# ADSR_Waveform_v1_1.net
KiCad netlist of a schematic drawn in EAGLE
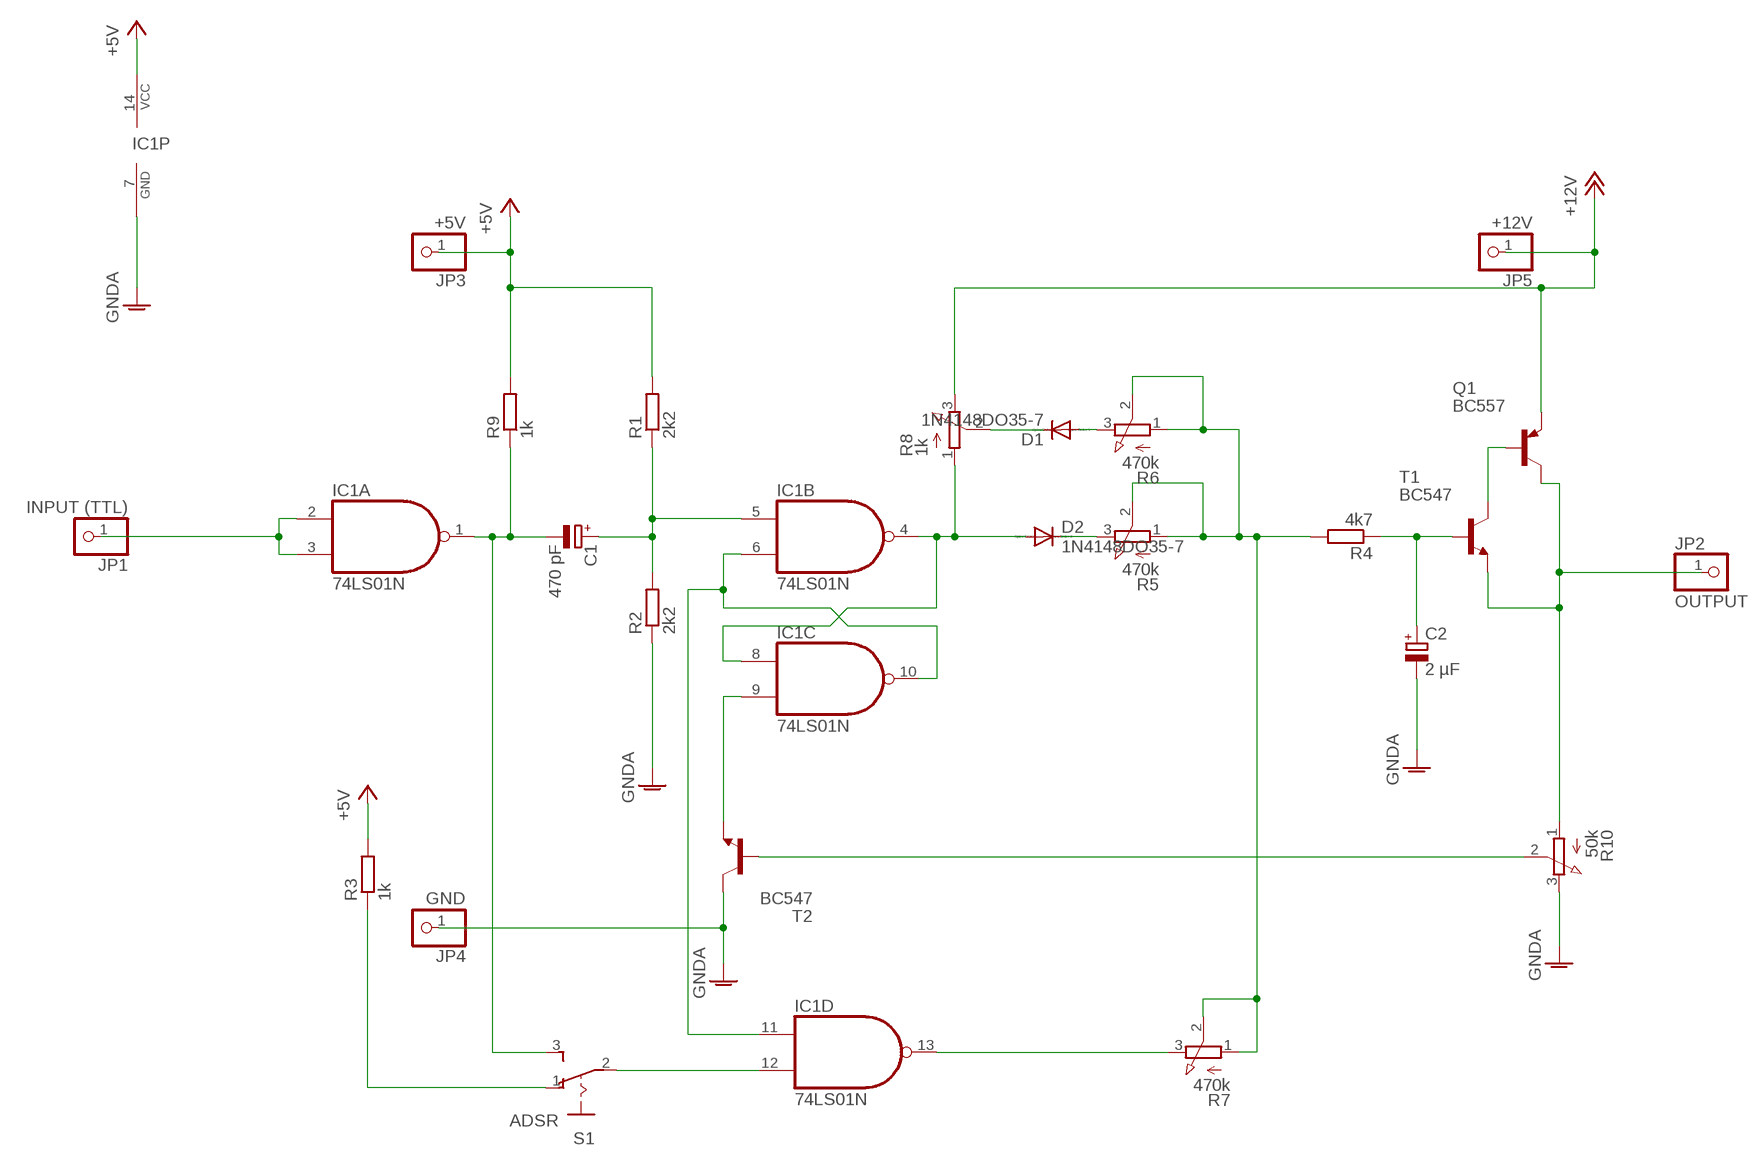
[diagram p0: schematic, sheet 1]

(export (version "E")
  (design (tool "Eeschema 10.0.6"))
  (components
    (comp (ref "C1")
      (value "470 pF")
      (footprint "eagle-import:E5-5")
      (libsource (lib "eagle-import") (part "CPOL-EUE5-5"))
    )
    (comp (ref "C2")
      (value "2 µF")
      (footprint "eagle-import:E5-5")
      (libsource (lib "eagle-import") (part "CPOL-EUE5-5"))
    )
    (comp (ref "D1")
      (value "1N4148DO35-7")
      (footprint "eagle-import:DO35-7")
      (libsource (lib "eagle-import") (part "1N4148DO35-7"))
    )
    (comp (ref "D2")
      (value "1N4148DO35-7")
      (footprint "eagle-import:DO35-7")
      (libsource (lib "eagle-import") (part "1N4148DO35-7"))
    )
    (comp (ref "IC1")
      (value "74LS01N")
      (footprint "eagle-import:DIL14")
      (libsource (lib "eagle-import") (part "7401NLS"))
    )
    (comp (ref "JP1")
      (value "INPUT (TTL)")
      (footprint "eagle-import:1X01")
      (libsource (lib "eagle-import") (part "PINHD-1X1"))
    )
    (comp (ref "JP2")
      (value "OUTPUT")
      (footprint "eagle-import:1X01")
      (libsource (lib "eagle-import") (part "PINHD-1X1"))
    )
    (comp (ref "JP3")
      (value "+5V")
      (footprint "eagle-import:1X01")
      (libsource (lib "eagle-import") (part "PINHD-1X1"))
    )
    (comp (ref "JP4")
      (value "GND")
      (footprint "eagle-import:1X01")
      (libsource (lib "eagle-import") (part "PINHD-1X1"))
    )
    (comp (ref "JP5")
      (value "+12V")
      (footprint "eagle-import:1X01")
      (libsource (lib "eagle-import") (part "PINHD-1X1"))
    )
    (comp (ref "Q1")
      (value "BC557")
      (footprint "eagle-import:TO92")
      (libsource (lib "eagle-import") (part "BC557"))
    )
    (comp (ref "R1")
      (value "2k2")
      (footprint "eagle-import:0204_5")
      (libsource (lib "eagle-import") (part "R-EU_0204/5"))
    )
    (comp (ref "R2")
      (value "2k2")
      (footprint "eagle-import:0204_5")
      (libsource (lib "eagle-import") (part "R-EU_0204/5"))
    )
    (comp (ref "R3")
      (value "1k")
      (footprint "eagle-import:0204_5")
      (libsource (lib "eagle-import") (part "R-EU_0204/5"))
    )
    (comp (ref "R4")
      (value "4k7")
      (footprint "eagle-import:0204_5")
      (libsource (lib "eagle-import") (part "R-EU_0204/5"))
    )
    (comp (ref "R5")
      (value "470k")
      (footprint "eagle-import:3RP_1610N")
      (libsource (lib "eagle-import") (part "3RP/1610N"))
    )
    (comp (ref "R6")
      (value "470k")
      (footprint "eagle-import:3RP_1610N")
      (libsource (lib "eagle-import") (part "3RP/1610N"))
    )
    (comp (ref "R7")
      (value "470k")
      (footprint "eagle-import:3RP_1610N")
      (libsource (lib "eagle-import") (part "3RP/1610N"))
    )
    (comp (ref "R8")
      (value "1k")
      (footprint "eagle-import:3RP_1610N")
      (libsource (lib "eagle-import") (part "3RP/1610N"))
    )
    (comp (ref "R9")
      (value "1k")
      (footprint "eagle-import:0204_5")
      (libsource (lib "eagle-import") (part "R-EU_0204/5"))
    )
    (comp (ref "R10")
      (value "50k")
      (footprint "eagle-import:3RP_1610N")
      (libsource (lib "eagle-import") (part "3RP/1610N"))
    )
    (comp (ref "S1")
      (value "ADSR")
      (footprint "eagle-import:255SB")
      (libsource (lib "eagle-import") (part "255SB"))
    )
    (comp (ref "T1")
      (value "BC547")
      (footprint "eagle-import:TO92")
      (libsource (lib "eagle-import") (part "BC547"))
    )
    (comp (ref "T2")
      (value "BC547")
      (footprint "eagle-import:TO92")
      (libsource (lib "eagle-import") (part "BC547"))
    )
  )
  (nets
    (net (code "1") (name "+5V") (class "Default")
      (node (ref "IC1") (pin "14") (pinfunction "VCC_14") (pintype "power_in"))
      (node (ref "JP3") (pin "1") (pinfunction "1_1") (pintype "passive"))
      (node (ref "R1") (pin "2") (pinfunction "2_2") (pintype "passive"))
      (node (ref "R3") (pin "2") (pinfunction "2_2") (pintype "passive"))
      (node (ref "R9") (pin "2") (pinfunction "2_2") (pintype "passive"))
    )
    (net (code "2") (name "+12V") (class "Default")
      (node (ref "JP5") (pin "1") (pinfunction "1_1") (pintype "passive"))
      (node (ref "Q1") (pin "1") (pinfunction "E_1") (pintype "passive"))
      (node (ref "R8") (pin "3") (pinfunction "E_3") (pintype "passive"))
    )
    (net (code "3") (name "GNDA") (class "Default")
      (node (ref "C2") (pin "-") (pinfunction "-_-") (pintype "passive"))
      (node (ref "IC1") (pin "7") (pinfunction "GND_7") (pintype "power_in"))
      (node (ref "JP4") (pin "1") (pinfunction "1_1") (pintype "passive"))
      (node (ref "R10") (pin "3") (pinfunction "E_3") (pintype "passive"))
      (node (ref "R2") (pin "1") (pinfunction "1_1") (pintype "passive"))
      (node (ref "T2") (pin "3") (pinfunction "C_3") (pintype "passive"))
    )
    (net (code "4") (name "Net-(IC1A-I0)") (class "Default")
      (node (ref "IC1") (pin "2") (pinfunction "I0_2") (pintype "input"))
      (node (ref "IC1") (pin "3") (pinfunction "I1_3") (pintype "input"))
      (node (ref "JP1") (pin "1") (pinfunction "1_1") (pintype "passive"))
    )
    (net (code "5") (name "Net-(IC1A-O)") (class "Default")
      (node (ref "C1") (pin "-") (pinfunction "-_-") (pintype "passive"))
      (node (ref "IC1") (pin "1") (pinfunction "O_1") (pintype "open_collector"))
      (node (ref "R9") (pin "1") (pinfunction "1_1") (pintype "passive"))
      (node (ref "S1") (pin "3") (pinfunction "S_3") (pintype "passive"))
    )
    (net (code "6") (name "Net-(IC1B-I0)") (class "Default")
      (node (ref "C1") (pin "+") (pinfunction "+_+") (pintype "passive"))
      (node (ref "IC1") (pin "5") (pinfunction "I0_5") (pintype "input"))
      (node (ref "R1") (pin "1") (pinfunction "1_1") (pintype "passive"))
      (node (ref "R2") (pin "2") (pinfunction "2_2") (pintype "passive"))
    )
    (net (code "7") (name "Net-(IC1B-I1)") (class "Default")
      (node (ref "IC1") (pin "10") (pinfunction "O_10") (pintype "open_collector"))
      (node (ref "IC1") (pin "11") (pinfunction "I0_11") (pintype "input"))
      (node (ref "IC1") (pin "6") (pinfunction "I1_6") (pintype "input"))
    )
    (net (code "8") (name "Net-(IC1B-O)") (class "Default")
      (node (ref "D2") (pin "A") (pinfunction "A_A") (pintype "passive"))
      (node (ref "IC1") (pin "4") (pinfunction "O_4") (pintype "open_collector"))
      (node (ref "IC1") (pin "8") (pinfunction "I0_8") (pintype "input"))
      (node (ref "R8") (pin "1") (pinfunction "A_1") (pintype "passive"))
    )
    (net (code "9") (name "Net-(IC1C-I1)") (class "Default")
      (node (ref "IC1") (pin "9") (pinfunction "I1_9") (pintype "input"))
      (node (ref "T2") (pin "1") (pinfunction "E_1") (pintype "passive"))
    )
    (net (code "10") (name "Net-(IC1D-I1)") (class "Default")
      (node (ref "IC1") (pin "12") (pinfunction "I1_12") (pintype "input"))
      (node (ref "S1") (pin "2") (pinfunction "P_2") (pintype "passive"))
    )
    (net (code "11") (name "Net-(IC1D-O)") (class "Default")
      (node (ref "IC1") (pin "13") (pinfunction "O_13") (pintype "open_collector"))
      (node (ref "R7") (pin "3") (pinfunction "E_3") (pintype "passive"))
    )
    (net (code "12") (name "Net-(Q1-B)") (class "Default")
      (node (ref "Q1") (pin "2") (pinfunction "B_2") (pintype "passive"))
      (node (ref "T1") (pin "3") (pinfunction "C_3") (pintype "passive"))
    )
    (net (code "13") (name "Net-(Q1-C)") (class "Default")
      (node (ref "JP2") (pin "1") (pinfunction "1_1") (pintype "passive"))
      (node (ref "Q1") (pin "3") (pinfunction "C_3") (pintype "passive"))
      (node (ref "R10") (pin "1") (pinfunction "A_1") (pintype "passive"))
      (node (ref "T1") (pin "1") (pinfunction "E_1") (pintype "passive"))
    )
    (net (code "14") (name "Net-(R5-A)") (class "Default")
      (node (ref "R4") (pin "2") (pinfunction "2_2") (pintype "passive"))
      (node (ref "R5") (pin "1") (pinfunction "A_1") (pintype "passive"))
      (node (ref "R5") (pin "2") (pinfunction "S_2") (pintype "passive"))
      (node (ref "R6") (pin "1") (pinfunction "A_1") (pintype "passive"))
      (node (ref "R6") (pin "2") (pinfunction "S_2") (pintype "passive"))
      (node (ref "R7") (pin "1") (pinfunction "A_1") (pintype "passive"))
      (node (ref "R7") (pin "2") (pinfunction "S_2") (pintype "passive"))
    )
    (net (code "15") (name "Net-(R5-E)") (class "Default")
      (node (ref "D2") (pin "C") (pinfunction "C_C") (pintype "passive"))
      (node (ref "R5") (pin "3") (pinfunction "E_3") (pintype "passive"))
    )
    (net (code "16") (name "Net-(R6-E)") (class "Default")
      (node (ref "D1") (pin "A") (pinfunction "A_A") (pintype "passive"))
      (node (ref "R6") (pin "3") (pinfunction "E_3") (pintype "passive"))
    )
    (net (code "17") (name "Net-(R8-S)") (class "Default")
      (node (ref "D1") (pin "C") (pinfunction "C_C") (pintype "passive"))
      (node (ref "R8") (pin "2") (pinfunction "S_2") (pintype "passive"))
    )
    (net (code "18") (name "Net-(R10-S)") (class "Default")
      (node (ref "R10") (pin "2") (pinfunction "S_2") (pintype "passive"))
      (node (ref "T2") (pin "2") (pinfunction "B_2") (pintype "passive"))
    )
    (net (code "19") (name "Net-(S1-O)") (class "Default")
      (node (ref "R3") (pin "1") (pinfunction "1_1") (pintype "passive"))
      (node (ref "S1") (pin "1") (pinfunction "O_1") (pintype "passive"))
    )
    (net (code "20") (name "Net-(T1-B)") (class "Default")
      (node (ref "C2") (pin "+") (pinfunction "+_+") (pintype "passive"))
      (node (ref "R4") (pin "1") (pinfunction "1_1") (pintype "passive"))
      (node (ref "T1") (pin "2") (pinfunction "B_2") (pintype "passive"))
    )
  )
)
